# aurola-board.net
KiCad netlist of a schematic drawn in EAGLE
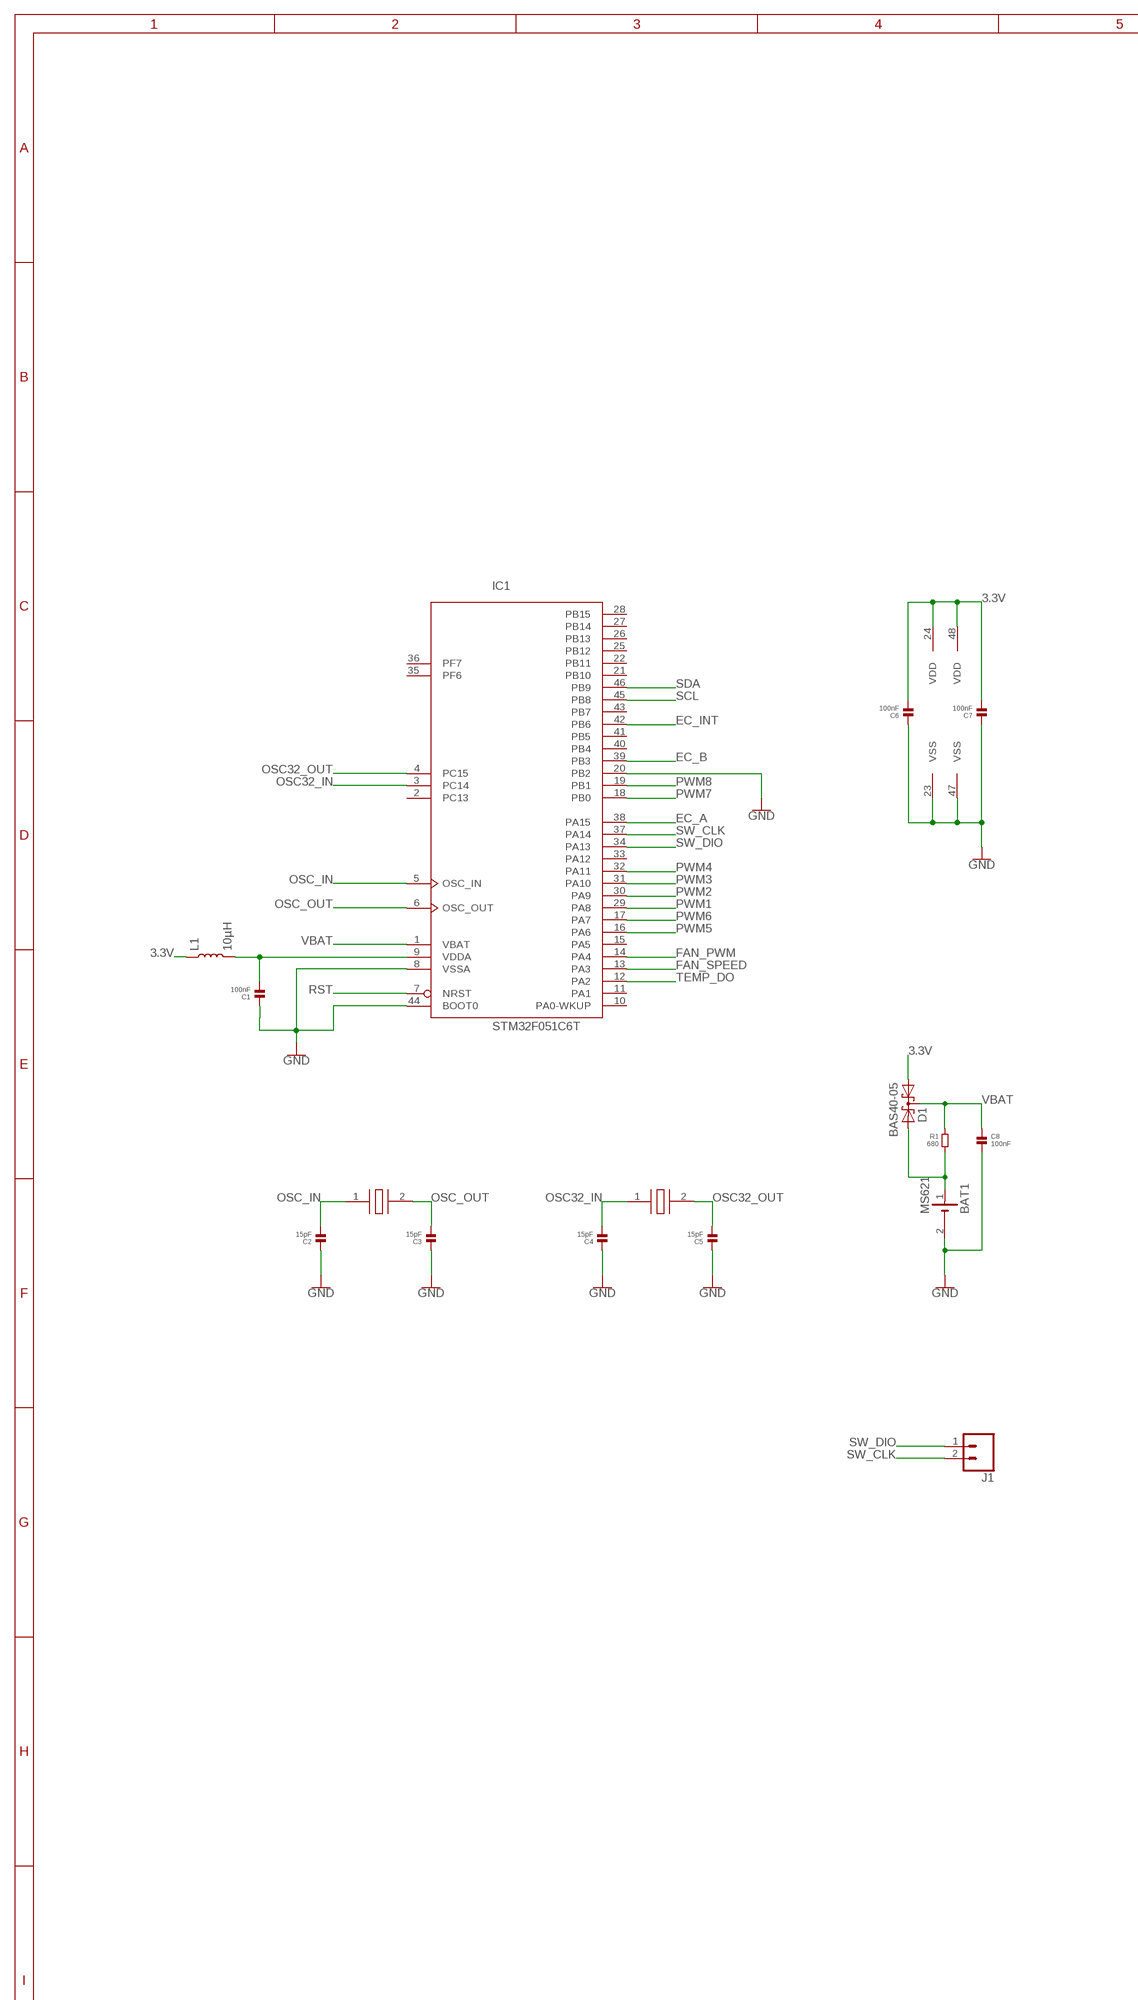
[diagram p0: schematic, sheet 1, part 1 of 2]
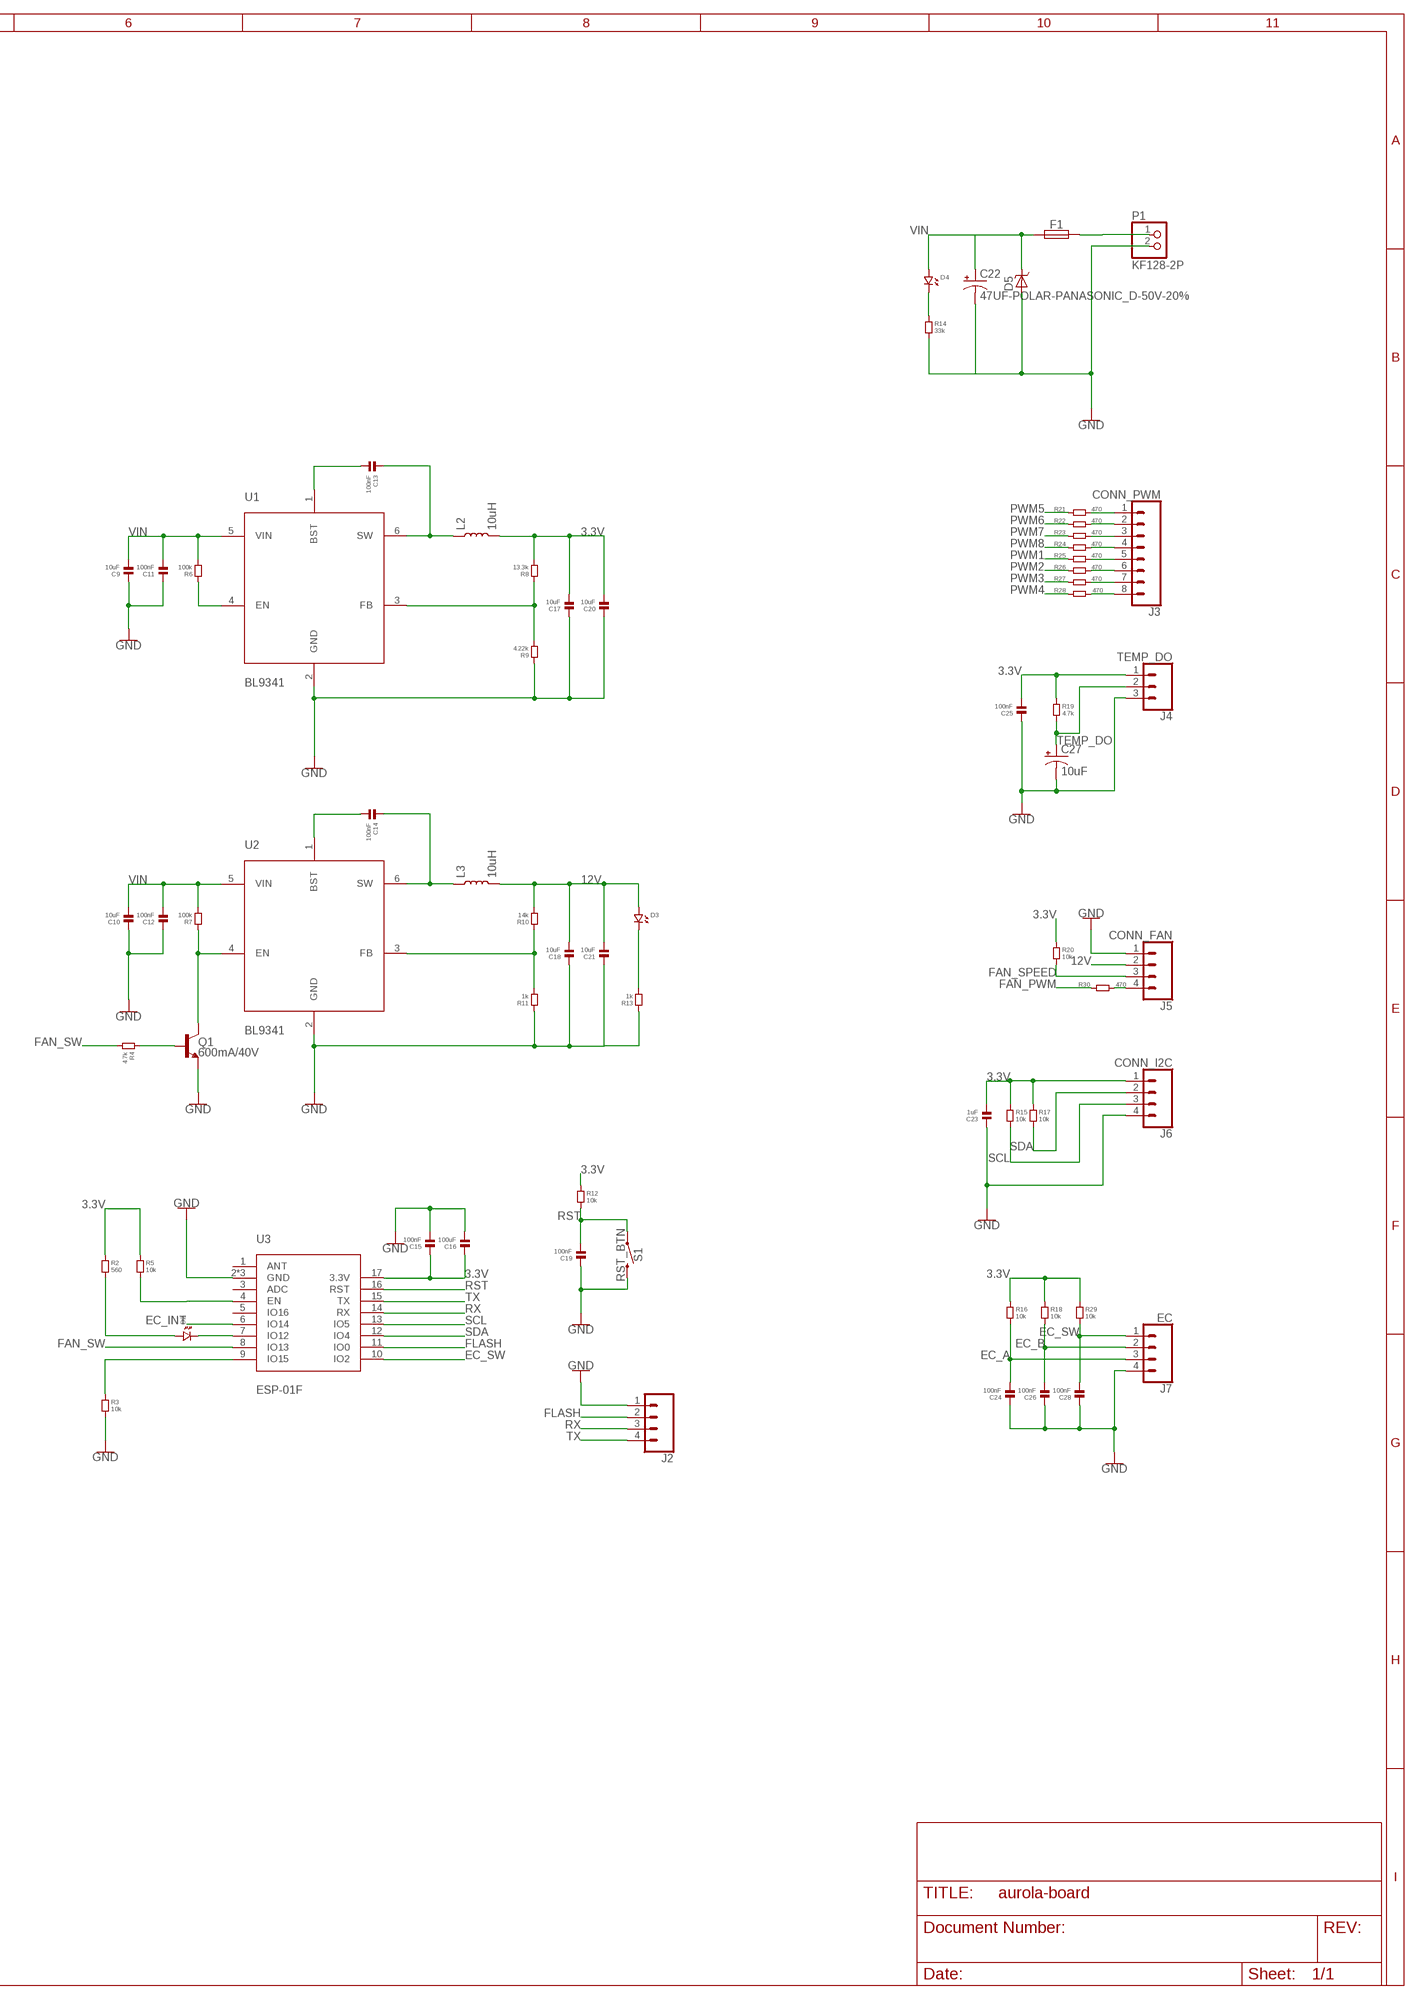
[diagram p1: schematic, sheet 1, part 2 of 2]

(export (version "E")
  (design (tool "Eeschema 10.0.6"))
  (components
    (comp (ref "BAT1")
      (value "MS621")
      (footprint "eagle-import:SMT_BAT")
      (libsource (lib "eagle-import") (part "MS621"))
    )
    (comp (ref "C1")
      (value "100nF")
      (footprint "eagle-import:0603")
      (libsource (lib "eagle-import") (part "CAPACITOR.0603"))
    )
    (comp (ref "C2")
      (value "15pF")
      (footprint "eagle-import:0603")
      (libsource (lib "eagle-import") (part "CAPACITOR.0603"))
    )
    (comp (ref "C3")
      (value "15pF")
      (footprint "eagle-import:0603")
      (libsource (lib "eagle-import") (part "CAPACITOR.0603"))
    )
    (comp (ref "C4")
      (value "15pF")
      (footprint "eagle-import:0603")
      (libsource (lib "eagle-import") (part "CAPACITOR.0603"))
    )
    (comp (ref "C5")
      (value "15pF")
      (footprint "eagle-import:0603")
      (libsource (lib "eagle-import") (part "CAPACITOR.0603"))
    )
    (comp (ref "C6")
      (value "100nF")
      (footprint "eagle-import:0603")
      (libsource (lib "eagle-import") (part "CAPACITOR.0603"))
    )
    (comp (ref "C7")
      (value "100nF")
      (footprint "eagle-import:0603")
      (libsource (lib "eagle-import") (part "CAPACITOR.0603"))
    )
    (comp (ref "C8")
      (value "100nF")
      (footprint "eagle-import:0603")
      (libsource (lib "eagle-import") (part "CAPACITOR.0603"))
    )
    (comp (ref "C9")
      (value "10uF")
      (footprint "eagle-import:1206")
      (libsource (lib "eagle-import") (part "CAPACITOR.1206"))
    )
    (comp (ref "C10")
      (value "10uF")
      (footprint "eagle-import:1206")
      (libsource (lib "eagle-import") (part "CAPACITOR.1206"))
    )
    (comp (ref "C11")
      (value "100nF")
      (footprint "eagle-import:0805")
      (libsource (lib "eagle-import") (part "CAPACITOR.0805"))
    )
    (comp (ref "C12")
      (value "100nF")
      (footprint "eagle-import:0805")
      (libsource (lib "eagle-import") (part "CAPACITOR.0805"))
    )
    (comp (ref "C13")
      (value "100nF")
      (footprint "eagle-import:0603")
      (libsource (lib "eagle-import") (part "CAPACITOR.0603"))
    )
    (comp (ref "C14")
      (value "100nF")
      (footprint "eagle-import:0603")
      (libsource (lib "eagle-import") (part "CAPACITOR.0603"))
    )
    (comp (ref "C15")
      (value "100nF")
      (footprint "eagle-import:0603")
      (libsource (lib "eagle-import") (part "CAPACITOR.0603"))
    )
    (comp (ref "C16")
      (value "100uF")
      (footprint "eagle-import:1210")
      (libsource (lib "eagle-import") (part "CAPACITOR.1210"))
    )
    (comp (ref "C17")
      (value "10uF")
      (footprint "eagle-import:1206")
      (libsource (lib "eagle-import") (part "CAPACITOR.1206"))
    )
    (comp (ref "C18")
      (value "10uF")
      (footprint "eagle-import:1206")
      (libsource (lib "eagle-import") (part "CAPACITOR.1206"))
    )
    (comp (ref "C19")
      (value "100nF")
      (footprint "eagle-import:0603")
      (libsource (lib "eagle-import") (part "CAPACITOR.0603"))
    )
    (comp (ref "C20")
      (value "10uF")
      (footprint "eagle-import:1206")
      (libsource (lib "eagle-import") (part "CAPACITOR.1206"))
    )
    (comp (ref "C21")
      (value "10uF")
      (footprint "eagle-import:1206")
      (libsource (lib "eagle-import") (part "CAPACITOR.1206"))
    )
    (comp (ref "C22")
      (value "47UF-POLAR-PANASONIC_D-50V-20%")
      (footprint "eagle-import:PANASONIC_D")
      (libsource (lib "eagle-import") (part "47UF-POLAR-PANASONIC_D-50V-20%"))
    )
    (comp (ref "C23")
      (value "1uF")
      (footprint "eagle-import:0603")
      (libsource (lib "eagle-import") (part "CAPACITOR.0603"))
    )
    (comp (ref "C24")
      (value "100nF")
      (footprint "eagle-import:0603")
      (libsource (lib "eagle-import") (part "CAPACITOR.0603"))
    )
    (comp (ref "C25")
      (value "100nF")
      (footprint "eagle-import:0603")
      (libsource (lib "eagle-import") (part "CAPACITOR.0603"))
    )
    (comp (ref "C26")
      (value "100nF")
      (footprint "eagle-import:0603")
      (libsource (lib "eagle-import") (part "CAPACITOR.0603"))
    )
    (comp (ref "C27")
      (value "10uF")
      (footprint "eagle-import:EIA3216")
      (libsource (lib "eagle-import") (part "10UF-POLAR-EIA3216-16V-10%(TANT)"))
    )
    (comp (ref "C28")
      (value "100nF")
      (footprint "eagle-import:0603")
      (libsource (lib "eagle-import") (part "CAPACITOR.0603"))
    )
    (comp (ref "D1")
      (value "BAS40-05")
      (footprint "eagle-import:SOT23")
      (libsource (lib "eagle-import") (part "BAS40-05"))
    )
    (comp (ref "D2")
      (value "LED.0603")
      (footprint "eagle-import:0603.LED")
      (libsource (lib "eagle-import") (part "LED.0603"))
    )
    (comp (ref "D3")
      (value "LED.0603")
      (footprint "eagle-import:0603.LED")
      (libsource (lib "eagle-import") (part "LED.0603"))
    )
    (comp (ref "D4")
      (value "LED.0603")
      (footprint "eagle-import:0603.LED")
      (libsource (lib "eagle-import") (part "LED.0603"))
    )
    (comp (ref "D5")
      (value "D_TVS-SMA")
      (footprint "eagle-import:SMA_DO214AC")
      (libsource (lib "eagle-import") (part "D_TVS-SMA"))
    )
    (comp (ref "F1")
      (value "FUSE-1206")
      (footprint "eagle-import:C1206")
      (libsource (lib "eagle-import") (part "FUSE-1206"))
    )
    (comp (ref "IC1")
      (value "STM32F051C6T")
      (footprint "eagle-import:LQFP48")
      (libsource (lib "eagle-import") (part "STM32F051CT6"))
    )
    (comp (ref "J1")
      (value "CONN_02")
      (footprint "eagle-import:1X02")
      (libsource (lib "eagle-import") (part "CONN_02"))
    )
    (comp (ref "J2")
      (value "CONN_04")
      (footprint "eagle-import:1X04")
      (libsource (lib "eagle-import") (part "CONN_04"))
    )
    (comp (ref "J3")
      (value "CONN_PWM")
      (footprint "eagle-import:PH2.0_8P")
      (libsource (lib "eagle-import") (part "PH2.0_8P_SMD"))
    )
    (comp (ref "J4")
      (value "TEMP_DO")
      (footprint "eagle-import:PH2.0_3P")
      (libsource (lib "eagle-import") (part "PH2.0_3P_SMD"))
    )
    (comp (ref "J5")
      (value "CONN_FAN")
      (footprint "eagle-import:PH2.0_4P")
      (libsource (lib "eagle-import") (part "PH2.0_4P_SMD"))
    )
    (comp (ref "J6")
      (value "CONN_I2C")
      (footprint "eagle-import:PH2.0_4P")
      (libsource (lib "eagle-import") (part "PH2.0_4P_SMD"))
    )
    (comp (ref "J7")
      (value "EC")
      (footprint "eagle-import:PH2.0_4P")
      (libsource (lib "eagle-import") (part "PH2.0_4P_SMD"))
    )
    (comp (ref "L1")
      (value "10µH")
      (footprint "eagle-import:0805")
      (libsource (lib "eagle-import") (part "INDUCTOR-0805-3.3UH"))
    )
    (comp (ref "L2")
      (value "10uH")
      (footprint "eagle-import:CR54")
      (libsource (lib "eagle-import") (part "INDUCTOR-CR54-47UH"))
    )
    (comp (ref "L3")
      (value "10uH")
      (footprint "eagle-import:CR54")
      (libsource (lib "eagle-import") (part "INDUCTOR-CR54-47UH"))
    )
    (comp (ref "P1")
      (value "KF128-2P")
      (footprint "eagle-import:2P-2.54MM")
      (libsource (lib "eagle-import") (part "KF128-2P"))
    )
    (comp (ref "Q1")
      (value "600mA/40V")
      (footprint "eagle-import:SOT23-3")
      (libsource (lib "eagle-import") (part "TRANS_NPN-MMBT2222AL"))
    )
    (comp (ref "R1")
      (value "680")
      (footprint "eagle-import:0805")
      (libsource (lib "eagle-import") (part "RESISTOR.0805"))
    )
    (comp (ref "R2")
      (value "560")
      (footprint "eagle-import:0603")
      (libsource (lib "eagle-import") (part "RESISTOR.0603"))
    )
    (comp (ref "R3")
      (value "10k")
      (footprint "eagle-import:0603")
      (libsource (lib "eagle-import") (part "RESISTOR.0603"))
    )
    (comp (ref "R4")
      (value "4.7k")
      (footprint "eagle-import:0603")
      (libsource (lib "eagle-import") (part "RESISTOR.0603"))
    )
    (comp (ref "R5")
      (value "10k")
      (footprint "eagle-import:0603")
      (libsource (lib "eagle-import") (part "RESISTOR.0603"))
    )
    (comp (ref "R6")
      (value "100k")
      (footprint "eagle-import:0603")
      (libsource (lib "eagle-import") (part "RESISTOR.0603"))
    )
    (comp (ref "R7")
      (value "100k")
      (footprint "eagle-import:0603")
      (libsource (lib "eagle-import") (part "RESISTOR.0603"))
    )
    (comp (ref "R8")
      (value "13.3k")
      (footprint "eagle-import:0603")
      (libsource (lib "eagle-import") (part "RESISTOR.0603"))
    )
    (comp (ref "R9")
      (value "4.22k")
      (footprint "eagle-import:0603")
      (libsource (lib "eagle-import") (part "RESISTOR.0603"))
    )
    (comp (ref "R10")
      (value "14k")
      (footprint "eagle-import:0603")
      (libsource (lib "eagle-import") (part "RESISTOR.0603"))
    )
    (comp (ref "R11")
      (value "1k")
      (footprint "eagle-import:0603")
      (libsource (lib "eagle-import") (part "RESISTOR.0603"))
    )
    (comp (ref "R12")
      (value "10k")
      (footprint "eagle-import:0603")
      (libsource (lib "eagle-import") (part "RESISTOR.0603"))
    )
    (comp (ref "R13")
      (value "1k")
      (footprint "eagle-import:0603")
      (libsource (lib "eagle-import") (part "RESISTOR.0603"))
    )
    (comp (ref "R14")
      (value "33k")
      (footprint "eagle-import:0603")
      (libsource (lib "eagle-import") (part "RESISTOR.0603"))
    )
    (comp (ref "R15")
      (value "10k")
      (footprint "eagle-import:0603")
      (libsource (lib "eagle-import") (part "RESISTOR.0603"))
    )
    (comp (ref "R16")
      (value "10k")
      (footprint "eagle-import:0603")
      (libsource (lib "eagle-import") (part "RESISTOR.0603"))
    )
    (comp (ref "R17")
      (value "10k")
      (footprint "eagle-import:0603")
      (libsource (lib "eagle-import") (part "RESISTOR.0603"))
    )
    (comp (ref "R18")
      (value "10k")
      (footprint "eagle-import:0603")
      (libsource (lib "eagle-import") (part "RESISTOR.0603"))
    )
    (comp (ref "R19")
      (value "4.7k")
      (footprint "eagle-import:0603")
      (libsource (lib "eagle-import") (part "RESISTOR.0603"))
    )
    (comp (ref "R20")
      (value "10k")
      (footprint "eagle-import:0603")
      (libsource (lib "eagle-import") (part "RESISTOR.0603"))
    )
    (comp (ref "R21")
      (value "470")
      (footprint "eagle-import:0603")
      (libsource (lib "eagle-import") (part "RESISTOR.0603"))
    )
    (comp (ref "R22")
      (value "470")
      (footprint "eagle-import:0603")
      (libsource (lib "eagle-import") (part "RESISTOR.0603"))
    )
    (comp (ref "R23")
      (value "470")
      (footprint "eagle-import:0603")
      (libsource (lib "eagle-import") (part "RESISTOR.0603"))
    )
    (comp (ref "R24")
      (value "470")
      (footprint "eagle-import:0603")
      (libsource (lib "eagle-import") (part "RESISTOR.0603"))
    )
    (comp (ref "R25")
      (value "470")
      (footprint "eagle-import:0603")
      (libsource (lib "eagle-import") (part "RESISTOR.0603"))
    )
    (comp (ref "R26")
      (value "470")
      (footprint "eagle-import:0603")
      (libsource (lib "eagle-import") (part "RESISTOR.0603"))
    )
    (comp (ref "R27")
      (value "470")
      (footprint "eagle-import:0603")
      (libsource (lib "eagle-import") (part "RESISTOR.0603"))
    )
    (comp (ref "R28")
      (value "470")
      (footprint "eagle-import:0603")
      (libsource (lib "eagle-import") (part "RESISTOR.0603"))
    )
    (comp (ref "R29")
      (value "10k")
      (footprint "eagle-import:0603")
      (libsource (lib "eagle-import") (part "RESISTOR.0603"))
    )
    (comp (ref "R30")
      (value "470")
      (footprint "eagle-import:0603")
      (libsource (lib "eagle-import") (part "RESISTOR.0603"))
    )
    (comp (ref "S1")
      (value "RST_BTN")
      (footprint "eagle-import:TACTILE_SWITCH_SMD_6.0X3.5MM")
      (libsource (lib "eagle-import") (part "MOMENTARY-SWITCH-SPST-SMD-6.0X3.5MM"))
    )
    (comp (ref "U1")
      (value "BL9341")
      (footprint "eagle-import:SOT23-6")
      (libsource (lib "eagle-import") (part "BL9341"))
    )
    (comp (ref "U2")
      (value "BL9341")
      (footprint "eagle-import:SOT23-6")
      (libsource (lib "eagle-import") (part "BL9341"))
    )
    (comp (ref "U3")
      (value "ESP-01F")
      (footprint "eagle-import:ESP-01F")
      (libsource (lib "eagle-import") (part "ESP-01F"))
    )
    (comp (ref "Y1")
      (value "NX5032CA-8MHZ")
      (footprint "eagle-import:NX5032CA-8MHZ")
      (libsource (lib "eagle-import") (part "NX5032CA-8MHZ"))
    )
    (comp (ref "Y2")
      (value "32.768KHZ-FC-135")
      (footprint "eagle-import:32.768KHZ-FC-135")
      (libsource (lib "eagle-import") (part "32.768KHZ-FC-135"))
    )
  )
  (nets
    (net (code "1") (name "/3.3V") (class "Default")
      (node (ref "C15") (pin "1") (pinfunction "1_1") (pintype "bidirectional"))
      (node (ref "C16") (pin "1") (pinfunction "1_1") (pintype "bidirectional"))
      (node (ref "C17") (pin "2") (pinfunction "2_2") (pintype "bidirectional"))
      (node (ref "C20") (pin "2") (pinfunction "2_2") (pintype "bidirectional"))
      (node (ref "C23") (pin "2") (pinfunction "2_2") (pintype "bidirectional"))
      (node (ref "C25") (pin "2") (pinfunction "2_2") (pintype "bidirectional"))
      (node (ref "C6") (pin "2") (pinfunction "2_2") (pintype "bidirectional"))
      (node (ref "C7") (pin "2") (pinfunction "2_2") (pintype "bidirectional"))
      (node (ref "D1") (pin "1") (pinfunction "A1_1") (pintype "passive"))
      (node (ref "IC1") (pin "24") (pinfunction "VDD_24") (pintype "power_in"))
      (node (ref "IC1") (pin "48") (pinfunction "VDD_48") (pintype "power_in"))
      (node (ref "J4") (pin "1") (pinfunction "1_1") (pintype "passive"))
      (node (ref "J6") (pin "1") (pinfunction "1_1") (pintype "passive"))
      (node (ref "L1") (pin "1") (pinfunction "1_1") (pintype "passive"))
      (node (ref "L2") (pin "P$2") (pinfunction "2_P$2") (pintype "passive"))
      (node (ref "R12") (pin "1") (pinfunction "1_1") (pintype "bidirectional"))
      (node (ref "R15") (pin "1") (pinfunction "1_1") (pintype "bidirectional"))
      (node (ref "R16") (pin "1") (pinfunction "1_1") (pintype "bidirectional"))
      (node (ref "R17") (pin "1") (pinfunction "1_1") (pintype "bidirectional"))
      (node (ref "R18") (pin "1") (pinfunction "1_1") (pintype "bidirectional"))
      (node (ref "R19") (pin "1") (pinfunction "1_1") (pintype "bidirectional"))
      (node (ref "R2") (pin "1") (pinfunction "1_1") (pintype "bidirectional"))
      (node (ref "R20") (pin "1") (pinfunction "1_1") (pintype "bidirectional"))
      (node (ref "R29") (pin "1") (pinfunction "1_1") (pintype "bidirectional"))
      (node (ref "R5") (pin "1") (pinfunction "1_1") (pintype "bidirectional"))
      (node (ref "R8") (pin "2") (pinfunction "2_2") (pintype "bidirectional"))
      (node (ref "U3") (pin "17") (pinfunction "3.3V_17") (pintype "power_in"))
    )
    (net (code "2") (name "/12V") (class "Default")
      (node (ref "C18") (pin "2") (pinfunction "2_2") (pintype "bidirectional"))
      (node (ref "C21") (pin "2") (pinfunction "2_2") (pintype "bidirectional"))
      (node (ref "D3") (pin "P$1") (pinfunction "1_P$1") (pintype "bidirectional"))
      (node (ref "J5") (pin "2") (pinfunction "2_2") (pintype "passive"))
      (node (ref "L3") (pin "P$2") (pinfunction "2_P$2") (pintype "passive"))
      (node (ref "R10") (pin "2") (pinfunction "2_2") (pintype "bidirectional"))
    )
    (net (code "3") (name "/EC_A") (class "Default")
      (node (ref "C24") (pin "2") (pinfunction "2_2") (pintype "bidirectional"))
      (node (ref "IC1") (pin "38") (pinfunction "PA15_38") (pintype "bidirectional"))
      (node (ref "J7") (pin "3") (pinfunction "3_3") (pintype "passive"))
      (node (ref "R16") (pin "2") (pinfunction "2_2") (pintype "bidirectional"))
    )
    (net (code "4") (name "/EC_B") (class "Default")
      (node (ref "C26") (pin "2") (pinfunction "2_2") (pintype "bidirectional"))
      (node (ref "IC1") (pin "39") (pinfunction "PB3_39") (pintype "bidirectional"))
      (node (ref "J7") (pin "2") (pinfunction "2_2") (pintype "passive"))
      (node (ref "R18") (pin "2") (pinfunction "2_2") (pintype "bidirectional"))
    )
    (net (code "5") (name "/EC_INT") (class "Default")
      (node (ref "IC1") (pin "42") (pinfunction "PB6_42") (pintype "bidirectional"))
      (node (ref "U3") (pin "6") (pinfunction "IO14_6") (pintype "bidirectional"))
    )
    (net (code "6") (name "/EC_SW") (class "Default")
      (node (ref "C28") (pin "2") (pinfunction "2_2") (pintype "bidirectional"))
      (node (ref "J7") (pin "1") (pinfunction "1_1") (pintype "passive"))
      (node (ref "R29") (pin "2") (pinfunction "2_2") (pintype "bidirectional"))
      (node (ref "U3") (pin "10") (pinfunction "IO2_10") (pintype "bidirectional"))
    )
    (net (code "7") (name "/FAN_PWM") (class "Default")
      (node (ref "IC1") (pin "14") (pinfunction "PA4_14") (pintype "bidirectional"))
      (node (ref "R30") (pin "1") (pinfunction "1_1") (pintype "bidirectional"))
    )
    (net (code "8") (name "/FAN_SPEED") (class "Default")
      (node (ref "IC1") (pin "13") (pinfunction "PA3_13") (pintype "bidirectional"))
      (node (ref "J5") (pin "3") (pinfunction "3_3") (pintype "passive"))
      (node (ref "R20") (pin "2") (pinfunction "2_2") (pintype "bidirectional"))
    )
    (net (code "9") (name "/FAN_SW") (class "Default")
      (node (ref "R4") (pin "2") (pinfunction "2_2") (pintype "bidirectional"))
      (node (ref "U3") (pin "8") (pinfunction "IO13_8") (pintype "bidirectional"))
    )
    (net (code "10") (name "/FLASH") (class "Default")
      (node (ref "J2") (pin "2") (pinfunction "2_2") (pintype "passive"))
      (node (ref "U3") (pin "11") (pinfunction "IO0_11") (pintype "bidirectional"))
    )
    (net (code "11") (name "/OSC32_IN") (class "Default")
      (node (ref "C4") (pin "2") (pinfunction "2_2") (pintype "bidirectional"))
      (node (ref "IC1") (pin "3") (pinfunction "PC14_3") (pintype "bidirectional"))
      (node (ref "Y2") (pin "1") (pinfunction "1.XIN_1") (pintype "bidirectional"))
    )
    (net (code "12") (name "/OSC32_OUT") (class "Default")
      (node (ref "C5") (pin "2") (pinfunction "2_2") (pintype "bidirectional"))
      (node (ref "IC1") (pin "4") (pinfunction "PC15_4") (pintype "bidirectional"))
      (node (ref "Y2") (pin "2") (pinfunction "2.XIN_2") (pintype "bidirectional"))
    )
    (net (code "13") (name "/OSC_IN") (class "Default")
      (node (ref "C2") (pin "2") (pinfunction "2_2") (pintype "bidirectional"))
      (node (ref "IC1") (pin "5") (pinfunction "OSC_IN_5") (pintype "bidirectional"))
      (node (ref "Y1") (pin "1") (pinfunction "1.XIN_1") (pintype "bidirectional"))
    )
    (net (code "14") (name "/OSC_OUT") (class "Default")
      (node (ref "C3") (pin "2") (pinfunction "2_2") (pintype "bidirectional"))
      (node (ref "IC1") (pin "6") (pinfunction "OSC_OUT_6") (pintype "bidirectional"))
      (node (ref "Y1") (pin "2") (pinfunction "2.XOUT_2") (pintype "bidirectional"))
    )
    (net (code "15") (name "/PWM1") (class "Default")
      (node (ref "IC1") (pin "29") (pinfunction "PA8_29") (pintype "bidirectional"))
      (node (ref "R25") (pin "1") (pinfunction "1_1") (pintype "bidirectional"))
    )
    (net (code "16") (name "/PWM2") (class "Default")
      (node (ref "IC1") (pin "30") (pinfunction "PA9_30") (pintype "bidirectional"))
      (node (ref "R26") (pin "1") (pinfunction "1_1") (pintype "bidirectional"))
    )
    (net (code "17") (name "/PWM3") (class "Default")
      (node (ref "IC1") (pin "31") (pinfunction "PA10_31") (pintype "bidirectional"))
      (node (ref "R27") (pin "1") (pinfunction "1_1") (pintype "bidirectional"))
    )
    (net (code "18") (name "/PWM4") (class "Default")
      (node (ref "IC1") (pin "32") (pinfunction "PA11_32") (pintype "bidirectional"))
      (node (ref "R28") (pin "1") (pinfunction "1_1") (pintype "bidirectional"))
    )
    (net (code "19") (name "/PWM5") (class "Default")
      (node (ref "IC1") (pin "16") (pinfunction "PA6_16") (pintype "bidirectional"))
      (node (ref "R21") (pin "1") (pinfunction "1_1") (pintype "bidirectional"))
    )
    (net (code "20") (name "/PWM6") (class "Default")
      (node (ref "IC1") (pin "17") (pinfunction "PA7_17") (pintype "bidirectional"))
      (node (ref "R22") (pin "1") (pinfunction "1_1") (pintype "bidirectional"))
    )
    (net (code "21") (name "/PWM7") (class "Default")
      (node (ref "IC1") (pin "18") (pinfunction "PB0_18") (pintype "bidirectional"))
      (node (ref "R23") (pin "1") (pinfunction "1_1") (pintype "bidirectional"))
    )
    (net (code "22") (name "/PWM8") (class "Default")
      (node (ref "IC1") (pin "19") (pinfunction "PB1_19") (pintype "bidirectional"))
      (node (ref "R24") (pin "1") (pinfunction "1_1") (pintype "bidirectional"))
    )
    (net (code "23") (name "/RST") (class "Default")
      (node (ref "C19") (pin "2") (pinfunction "2_2") (pintype "bidirectional"))
      (node (ref "IC1") (pin "7") (pinfunction "NRST_7") (pintype "bidirectional"))
      (node (ref "R12") (pin "2") (pinfunction "2_2") (pintype "bidirectional"))
      (node (ref "S1") (pin "1") (pinfunction "1_1") (pintype "passive"))
      (node (ref "U3") (pin "16") (pinfunction "RST_16") (pintype "passive"))
    )
    (net (code "24") (name "/RX") (class "Default")
      (node (ref "J2") (pin "3") (pinfunction "3_3") (pintype "passive"))
      (node (ref "U3") (pin "14") (pinfunction "RX_14") (pintype "input"))
    )
    (net (code "25") (name "/SCL") (class "Default")
      (node (ref "IC1") (pin "45") (pinfunction "PB8_45") (pintype "bidirectional"))
      (node (ref "J6") (pin "3") (pinfunction "3_3") (pintype "passive"))
      (node (ref "R15") (pin "2") (pinfunction "2_2") (pintype "bidirectional"))
      (node (ref "U3") (pin "13") (pinfunction "IO5_13") (pintype "input"))
    )
    (net (code "26") (name "/SDA") (class "Default")
      (node (ref "IC1") (pin "46") (pinfunction "PB9_46") (pintype "bidirectional"))
      (node (ref "J6") (pin "2") (pinfunction "2_2") (pintype "passive"))
      (node (ref "R17") (pin "2") (pinfunction "2_2") (pintype "bidirectional"))
      (node (ref "U3") (pin "12") (pinfunction "IO4_12") (pintype "bidirectional"))
    )
    (net (code "27") (name "/SW_CLK") (class "Default")
      (node (ref "IC1") (pin "37") (pinfunction "PA14_37") (pintype "bidirectional"))
      (node (ref "J1") (pin "2") (pinfunction "2_2") (pintype "passive"))
    )
    (net (code "28") (name "/SW_DIO") (class "Default")
      (node (ref "IC1") (pin "34") (pinfunction "PA13_34") (pintype "bidirectional"))
      (node (ref "J1") (pin "1") (pinfunction "1_1") (pintype "passive"))
    )
    (net (code "29") (name "/TEMP_DO") (class "Default")
      (node (ref "C27") (pin "+") (pinfunction "+_+") (pintype "passive"))
      (node (ref "IC1") (pin "12") (pinfunction "PA2_12") (pintype "bidirectional"))
      (node (ref "J4") (pin "2") (pinfunction "2_2") (pintype "passive"))
      (node (ref "R19") (pin "2") (pinfunction "2_2") (pintype "bidirectional"))
    )
    (net (code "30") (name "/TX") (class "Default")
      (node (ref "J2") (pin "4") (pinfunction "4_4") (pintype "passive"))
      (node (ref "U3") (pin "15") (pinfunction "TX_15") (pintype "output"))
    )
    (net (code "31") (name "/VBAT") (class "Default")
      (node (ref "C8") (pin "1") (pinfunction "1_1") (pintype "bidirectional"))
      (node (ref "D1") (pin "3") (pinfunction "K1K2_3") (pintype "passive"))
      (node (ref "IC1") (pin "1") (pinfunction "VBAT_1") (pintype "power_in"))
      (node (ref "R1") (pin "1") (pinfunction "1_1") (pintype "bidirectional"))
    )
    (net (code "32") (name "/VIN") (class "Default")
      (node (ref "C10") (pin "2") (pinfunction "2_2") (pintype "bidirectional"))
      (node (ref "C11") (pin "2") (pinfunction "2_2") (pintype "bidirectional"))
      (node (ref "C12") (pin "2") (pinfunction "2_2") (pintype "bidirectional"))
      (node (ref "C22") (pin "+") (pinfunction "+_+") (pintype "passive"))
      (node (ref "C9") (pin "2") (pinfunction "2_2") (pintype "bidirectional"))
      (node (ref "D4") (pin "P$1") (pinfunction "1_P$1") (pintype "bidirectional"))
      (node (ref "D5") (pin "C") (pinfunction "C_C") (pintype "passive"))
      (node (ref "F1") (pin "1") (pinfunction "1_1") (pintype "passive"))
      (node (ref "R6") (pin "2") (pinfunction "2_2") (pintype "bidirectional"))
      (node (ref "R7") (pin "2") (pinfunction "2_2") (pintype "bidirectional"))
      (node (ref "U1") (pin "5") (pinfunction "VIN_5") (pintype "bidirectional"))
      (node (ref "U2") (pin "5") (pinfunction "VIN_5") (pintype "bidirectional"))
    )
    (net (code "33") (name "GND") (class "Default")
      (node (ref "BAT1") (pin "2") (pinfunction "-_2") (pintype "passive"))
      (node (ref "C1") (pin "1") (pinfunction "1_1") (pintype "bidirectional"))
      (node (ref "C10") (pin "1") (pinfunction "1_1") (pintype "bidirectional"))
      (node (ref "C11") (pin "1") (pinfunction "1_1") (pintype "bidirectional"))
      (node (ref "C12") (pin "1") (pinfunction "1_1") (pintype "bidirectional"))
      (node (ref "C15") (pin "2") (pinfunction "2_2") (pintype "bidirectional"))
      (node (ref "C16") (pin "2") (pinfunction "2_2") (pintype "bidirectional"))
      (node (ref "C17") (pin "1") (pinfunction "1_1") (pintype "bidirectional"))
      (node (ref "C18") (pin "1") (pinfunction "1_1") (pintype "bidirectional"))
      (node (ref "C19") (pin "1") (pinfunction "1_1") (pintype "bidirectional"))
      (node (ref "C2") (pin "1") (pinfunction "1_1") (pintype "bidirectional"))
      (node (ref "C20") (pin "1") (pinfunction "1_1") (pintype "bidirectional"))
      (node (ref "C21") (pin "1") (pinfunction "1_1") (pintype "bidirectional"))
      (node (ref "C22") (pin "-") (pinfunction "-_-") (pintype "passive"))
      (node (ref "C23") (pin "1") (pinfunction "1_1") (pintype "bidirectional"))
      (node (ref "C24") (pin "1") (pinfunction "1_1") (pintype "bidirectional"))
      (node (ref "C25") (pin "1") (pinfunction "1_1") (pintype "bidirectional"))
      (node (ref "C26") (pin "1") (pinfunction "1_1") (pintype "bidirectional"))
      (node (ref "C27") (pin "-") (pinfunction "-_-") (pintype "passive"))
      (node (ref "C28") (pin "1") (pinfunction "1_1") (pintype "bidirectional"))
      (node (ref "C3") (pin "1") (pinfunction "1_1") (pintype "bidirectional"))
      (node (ref "C4") (pin "1") (pinfunction "1_1") (pintype "bidirectional"))
      (node (ref "C5") (pin "1") (pinfunction "1_1") (pintype "bidirectional"))
      (node (ref "C6") (pin "1") (pinfunction "1_1") (pintype "bidirectional"))
      (node (ref "C7") (pin "1") (pinfunction "1_1") (pintype "bidirectional"))
      (node (ref "C8") (pin "2") (pinfunction "2_2") (pintype "bidirectional"))
      (node (ref "C9") (pin "1") (pinfunction "1_1") (pintype "bidirectional"))
      (node (ref "D5") (pin "A") (pinfunction "A_A") (pintype "passive"))
      (node (ref "IC1") (pin "20") (pinfunction "PB2_20") (pintype "bidirectional"))
      (node (ref "IC1") (pin "23") (pinfunction "VSS_23") (pintype "power_in"))
      (node (ref "IC1") (pin "44") (pinfunction "BOOT0_44") (pintype "input"))
      (node (ref "IC1") (pin "47") (pinfunction "VSS_47") (pintype "power_in"))
      (node (ref "IC1") (pin "8") (pinfunction "VSSA_8") (pintype "power_in"))
      (node (ref "J2") (pin "1") (pinfunction "1_1") (pintype "passive"))
      (node (ref "J4") (pin "3") (pinfunction "3_3") (pintype "passive"))
      (node (ref "J5") (pin "1") (pinfunction "1_1") (pintype "passive"))
      (node (ref "J6") (pin "4") (pinfunction "4_4") (pintype "passive"))
      (node (ref "J7") (pin "4") (pinfunction "4_4") (pintype "passive"))
      (node (ref "P1") (pin "2") (pinfunction "2_2") (pintype "passive"))
      (node (ref "Q1") (pin "2") (pinfunction "E_2") (pintype "passive"))
      (node (ref "R11") (pin "1") (pinfunction "1_1") (pintype "bidirectional"))
      (node (ref "R13") (pin "1") (pinfunction "1_1") (pintype "bidirectional"))
      (node (ref "R14") (pin "2") (pinfunction "2_2") (pintype "bidirectional"))
      (node (ref "R3") (pin "2") (pinfunction "2_2") (pintype "bidirectional"))
      (node (ref "R9") (pin "1") (pinfunction "1_1") (pintype "bidirectional"))
      (node (ref "S1") (pin "2") (pinfunction "2_2") (pintype "passive"))
      (node (ref "U1") (pin "2") (pinfunction "GND_2") (pintype "bidirectional"))
      (node (ref "U2") (pin "2") (pinfunction "GND_2") (pintype "bidirectional"))
      (node (ref "U3") (pin "18") (pinfunction "GND_18") (pintype "passive"))
      (node (ref "U3") (pin "19") (pinfunction "GND_19") (pintype "passive"))
      (node (ref "U3") (pin "2") (pinfunction "GND_2") (pintype "passive"))
    )
    (net (code "34") (name "Net-(BAT1-+)") (class "Default")
      (node (ref "BAT1") (pin "1") (pinfunction "+_1") (pintype "passive"))
      (node (ref "D1") (pin "2") (pinfunction "A2_2") (pintype "passive"))
      (node (ref "R1") (pin "2") (pinfunction "2_2") (pintype "bidirectional"))
    )
    (net (code "35") (name "Net-(D2-1)") (class "Default")
      (node (ref "D2") (pin "P$1") (pinfunction "1_P$1") (pintype "bidirectional"))
      (node (ref "R2") (pin "2") (pinfunction "2_2") (pintype "bidirectional"))
    )
    (net (code "36") (name "Net-(D2-2)") (class "Default")
      (node (ref "D2") (pin "P$2") (pinfunction "2_P$2") (pintype "bidirectional"))
      (node (ref "U3") (pin "7") (pinfunction "IO12_7") (pintype "bidirectional"))
    )
    (net (code "37") (name "Net-(D3-2)") (class "Default")
      (node (ref "D3") (pin "P$2") (pinfunction "2_P$2") (pintype "bidirectional"))
      (node (ref "R13") (pin "2") (pinfunction "2_2") (pintype "bidirectional"))
    )
    (net (code "38") (name "Net-(D4-2)") (class "Default")
      (node (ref "D4") (pin "P$2") (pinfunction "2_P$2") (pintype "bidirectional"))
      (node (ref "R14") (pin "1") (pinfunction "1_1") (pintype "bidirectional"))
    )
    (net (code "39") (name "Net-(F1-Pad2)") (class "Default")
      (node (ref "F1") (pin "2") (pinfunction "2_2") (pintype "passive"))
      (node (ref "P1") (pin "1") (pinfunction "1_1") (pintype "passive"))
    )
    (net (code "40") (name "Net-(IC1A-VDDA)") (class "Default")
      (node (ref "C1") (pin "2") (pinfunction "2_2") (pintype "bidirectional"))
      (node (ref "IC1") (pin "9") (pinfunction "VDDA_9") (pintype "power_in"))
      (node (ref "L1") (pin "2") (pinfunction "2_2") (pintype "passive"))
    )
    (net (code "41") (name "Net-(J3-Pad1)") (class "Default")
      (node (ref "J3") (pin "1") (pinfunction "1_1") (pintype "passive"))
      (node (ref "R21") (pin "2") (pinfunction "2_2") (pintype "bidirectional"))
    )
    (net (code "42") (name "Net-(J3-Pad2)") (class "Default")
      (node (ref "J3") (pin "2") (pinfunction "2_2") (pintype "passive"))
      (node (ref "R22") (pin "2") (pinfunction "2_2") (pintype "bidirectional"))
    )
    (net (code "43") (name "Net-(J3-Pad3)") (class "Default")
      (node (ref "J3") (pin "3") (pinfunction "3_3") (pintype "passive"))
      (node (ref "R23") (pin "2") (pinfunction "2_2") (pintype "bidirectional"))
    )
    (net (code "44") (name "Net-(J3-Pad4)") (class "Default")
      (node (ref "J3") (pin "4") (pinfunction "4_4") (pintype "passive"))
      (node (ref "R24") (pin "2") (pinfunction "2_2") (pintype "bidirectional"))
    )
    (net (code "45") (name "Net-(J3-Pad5)") (class "Default")
      (node (ref "J3") (pin "5") (pinfunction "5_5") (pintype "passive"))
      (node (ref "R25") (pin "2") (pinfunction "2_2") (pintype "bidirectional"))
    )
    (net (code "46") (name "Net-(J3-Pad6)") (class "Default")
      (node (ref "J3") (pin "6") (pinfunction "6_6") (pintype "passive"))
      (node (ref "R26") (pin "2") (pinfunction "2_2") (pintype "bidirectional"))
    )
    (net (code "47") (name "Net-(J3-Pad7)") (class "Default")
      (node (ref "J3") (pin "7") (pinfunction "7_7") (pintype "passive"))
      (node (ref "R27") (pin "2") (pinfunction "2_2") (pintype "bidirectional"))
    )
    (net (code "48") (name "Net-(J3-Pad8)") (class "Default")
      (node (ref "J3") (pin "8") (pinfunction "8_8") (pintype "passive"))
      (node (ref "R28") (pin "2") (pinfunction "2_2") (pintype "bidirectional"))
    )
    (net (code "49") (name "Net-(J5-Pad4)") (class "Default")
      (node (ref "J5") (pin "4") (pinfunction "4_4") (pintype "passive"))
      (node (ref "R30") (pin "2") (pinfunction "2_2") (pintype "bidirectional"))
    )
    (net (code "50") (name "Net-(L2-1)") (class "Default")
      (node (ref "C13") (pin "1") (pinfunction "1_1") (pintype "bidirectional"))
      (node (ref "L2") (pin "P$1") (pinfunction "1_P$1") (pintype "passive"))
      (node (ref "U1") (pin "6") (pinfunction "SW_6") (pintype "bidirectional"))
    )
    (net (code "51") (name "Net-(L3-1)") (class "Default")
      (node (ref "C14") (pin "1") (pinfunction "1_1") (pintype "bidirectional"))
      (node (ref "L3") (pin "P$1") (pinfunction "1_P$1") (pintype "passive"))
      (node (ref "U2") (pin "6") (pinfunction "SW_6") (pintype "bidirectional"))
    )
    (net (code "52") (name "Net-(Q1-B)") (class "Default")
      (node (ref "Q1") (pin "1") (pinfunction "B_1") (pintype "passive"))
      (node (ref "R4") (pin "1") (pinfunction "1_1") (pintype "bidirectional"))
    )
    (net (code "53") (name "Net-(Q1-C)") (class "Default")
      (node (ref "Q1") (pin "3") (pinfunction "C_3") (pintype "passive"))
      (node (ref "R7") (pin "1") (pinfunction "1_1") (pintype "bidirectional"))
      (node (ref "U2") (pin "4") (pinfunction "EN_4") (pintype "bidirectional"))
    )
    (net (code "54") (name "Net-(U1-BST)") (class "Default")
      (node (ref "C13") (pin "2") (pinfunction "2_2") (pintype "bidirectional"))
      (node (ref "U1") (pin "1") (pinfunction "BST_1") (pintype "bidirectional"))
    )
    (net (code "55") (name "Net-(U1-EN)") (class "Default")
      (node (ref "R6") (pin "1") (pinfunction "1_1") (pintype "bidirectional"))
      (node (ref "U1") (pin "4") (pinfunction "EN_4") (pintype "bidirectional"))
    )
    (net (code "56") (name "Net-(U1-FB)") (class "Default")
      (node (ref "R8") (pin "1") (pinfunction "1_1") (pintype "bidirectional"))
      (node (ref "R9") (pin "2") (pinfunction "2_2") (pintype "bidirectional"))
      (node (ref "U1") (pin "3") (pinfunction "FB_3") (pintype "bidirectional"))
    )
    (net (code "57") (name "Net-(U2-BST)") (class "Default")
      (node (ref "C14") (pin "2") (pinfunction "2_2") (pintype "bidirectional"))
      (node (ref "U2") (pin "1") (pinfunction "BST_1") (pintype "bidirectional"))
    )
    (net (code "58") (name "Net-(U2-FB)") (class "Default")
      (node (ref "R10") (pin "1") (pinfunction "1_1") (pintype "bidirectional"))
      (node (ref "R11") (pin "2") (pinfunction "2_2") (pintype "bidirectional"))
      (node (ref "U2") (pin "3") (pinfunction "FB_3") (pintype "bidirectional"))
    )
    (net (code "59") (name "Net-(U3-EN)") (class "Default")
      (node (ref "R5") (pin "2") (pinfunction "2_2") (pintype "bidirectional"))
      (node (ref "U3") (pin "4") (pinfunction "EN_4") (pintype "passive"))
    )
    (net (code "60") (name "Net-(U3-IO15)") (class "Default")
      (node (ref "R3") (pin "1") (pinfunction "1_1") (pintype "bidirectional"))
      (node (ref "U3") (pin "9") (pinfunction "IO15_9") (pintype "bidirectional"))
    )
    (net (code "61") (name "unconnected-(IC1A-PA0-WKUP-Pad10)") (class "Default")
      (node (ref "IC1") (pin "10") (pinfunction "PA0-WKUP_10") (pintype "bidirectional"))
    )
    (net (code "62") (name "unconnected-(IC1A-PA1-Pad11)") (class "Default")
      (node (ref "IC1") (pin "11") (pinfunction "PA1_11") (pintype "bidirectional"))
    )
    (net (code "63") (name "unconnected-(IC1A-PA5-Pad15)") (class "Default")
      (node (ref "IC1") (pin "15") (pinfunction "PA5_15") (pintype "bidirectional"))
    )
    (net (code "64") (name "unconnected-(IC1A-PA12-Pad33)") (class "Default")
      (node (ref "IC1") (pin "33") (pinfunction "PA12_33") (pintype "bidirectional"))
    )
    (net (code "65") (name "unconnected-(IC1A-PB4-Pad40)") (class "Default")
      (node (ref "IC1") (pin "40") (pinfunction "PB4_40") (pintype "bidirectional"))
    )
    (net (code "66") (name "unconnected-(IC1A-PB5-Pad41)") (class "Default")
      (node (ref "IC1") (pin "41") (pinfunction "PB5_41") (pintype "bidirectional"))
    )
    (net (code "67") (name "unconnected-(IC1A-PB7-Pad43)") (class "Default")
      (node (ref "IC1") (pin "43") (pinfunction "PB7_43") (pintype "bidirectional"))
    )
    (net (code "68") (name "unconnected-(IC1A-PB10-Pad21)") (class "Default")
      (node (ref "IC1") (pin "21") (pinfunction "PB10_21") (pintype "bidirectional"))
    )
    (net (code "69") (name "unconnected-(IC1A-PB11-Pad22)") (class "Default")
      (node (ref "IC1") (pin "22") (pinfunction "PB11_22") (pintype "bidirectional"))
    )
    (net (code "70") (name "unconnected-(IC1A-PB12-Pad25)") (class "Default")
      (node (ref "IC1") (pin "25") (pinfunction "PB12_25") (pintype "bidirectional"))
    )
    (net (code "71") (name "unconnected-(IC1A-PB13-Pad26)") (class "Default")
      (node (ref "IC1") (pin "26") (pinfunction "PB13_26") (pintype "bidirectional"))
    )
    (net (code "72") (name "unconnected-(IC1A-PB14-Pad27)") (class "Default")
      (node (ref "IC1") (pin "27") (pinfunction "PB14_27") (pintype "bidirectional"))
    )
    (net (code "73") (name "unconnected-(IC1A-PB15-Pad28)") (class "Default")
      (node (ref "IC1") (pin "28") (pinfunction "PB15_28") (pintype "bidirectional"))
    )
    (net (code "74") (name "unconnected-(IC1A-PC13-Pad2)") (class "Default")
      (node (ref "IC1") (pin "2") (pinfunction "PC13_2") (pintype "bidirectional"))
    )
    (net (code "75") (name "unconnected-(IC1A-PF6-Pad35)") (class "Default")
      (node (ref "IC1") (pin "35") (pinfunction "PF6_35") (pintype "bidirectional"))
    )
    (net (code "76") (name "unconnected-(IC1A-PF7-Pad36)") (class "Default")
      (node (ref "IC1") (pin "36") (pinfunction "PF7_36") (pintype "bidirectional"))
    )
    (net (code "77") (name "unconnected-(U3-ADC-Pad3)") (class "Default")
      (node (ref "U3") (pin "3") (pinfunction "ADC_3") (pintype "input"))
    )
    (net (code "78") (name "unconnected-(U3-ANT-Pad1)") (class "Default")
      (node (ref "U3") (pin "1") (pinfunction "ANT_1") (pintype "output"))
    )
    (net (code "79") (name "unconnected-(U3-IO16-Pad5)") (class "Default")
      (node (ref "U3") (pin "5") (pinfunction "IO16_5") (pintype "bidirectional"))
    )
  )
)
